# Top.net
KiCad netlist of a schematic drawn in Altium Designer
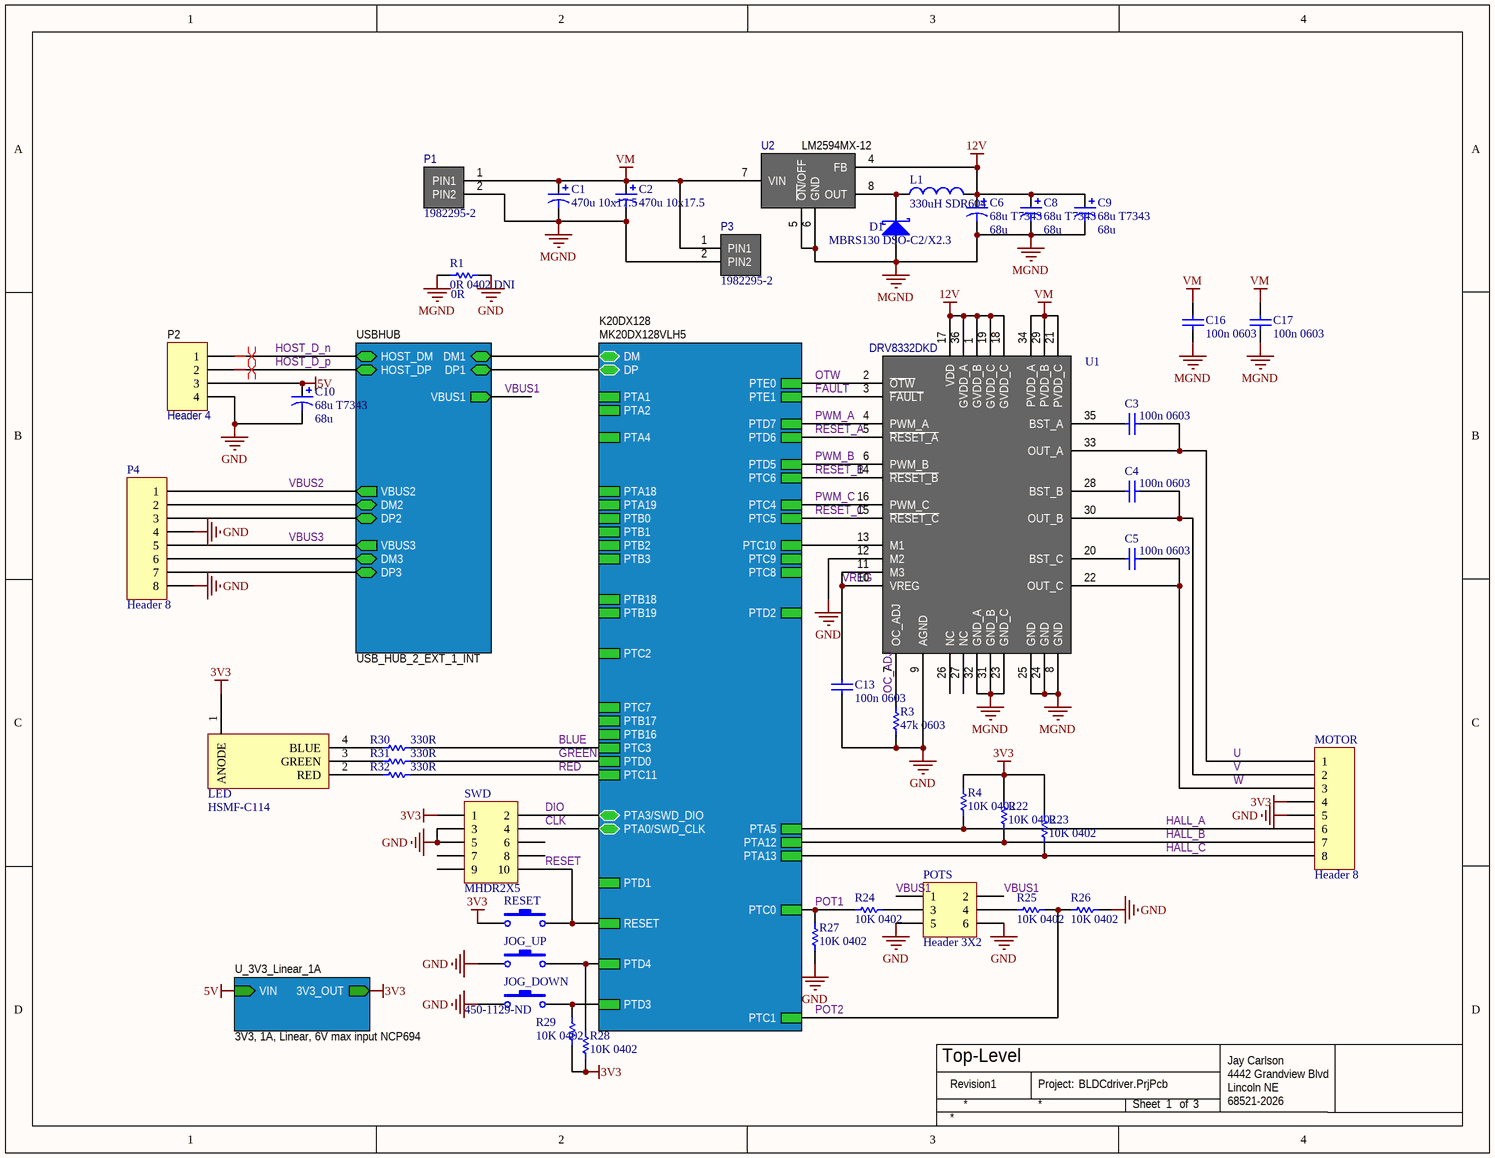
[diagram p0: Top.SchDoc]

(export (version "E")
  (design (tool "Eeschema 10.0.6"))
  (components
    (comp (ref "C1")
      (value "470u 10x17.5")
      (footprint "CAPPR5-10x17.5")
      (description "Polarized Capacitor (Radial)")
      (fields (field (name "PUBLISHER") "Altium Limited"))
      (libsource (lib "Miscellaneous Devices") (part "Cap Pol1"))
    )
    (comp (ref "C2")
      (value "470u 10x17.5")
      (footprint "CAPPR5-10x17.5")
      (description "Polarized Capacitor (Radial)")
      (fields (field (name "PUBLISHER") "Altium Limited"))
      (libsource (lib "Miscellaneous Devices") (part "Cap Pol1"))
    )
    (comp (ref "C3")
      (value "100n 0603")
      (footprint "CAPC1608N")
      (description "Capacitor")
      (fields (field (name "PUBLISHER") "Altium Limited"))
      (libsource (lib "Miscellaneous Devices") (part "Cap"))
    )
    (comp (ref "C4")
      (value "100n 0603")
      (footprint "CAPC1608N")
      (description "Capacitor")
      (fields (field (name "PUBLISHER") "Altium Limited"))
      (libsource (lib "Miscellaneous Devices") (part "Cap"))
    )
    (comp (ref "C5")
      (value "100n 0603")
      (footprint "CAPC1608N")
      (description "Capacitor")
      (fields (field (name "PUBLISHER") "Altium Limited"))
      (libsource (lib "Miscellaneous Devices") (part "Cap"))
    )
    (comp (ref "C6")
      (value "68u T7343")
      (footprint "TC7343-2917")
      (description "Polarized Capacitor (Radial)")
      (fields (field (name "ALTIUM_VALUE") "68u") (field (name "PUBLISHER") "Altium Limited"))
      (libsource (lib "Miscellaneous Devices") (part "Cap Pol1"))
    )
    (comp (ref "C8")
      (value "68u T7343")
      (footprint "TC7343-2917")
      (description "Polarized Capacitor (Radial)")
      (fields (field (name "ALTIUM_VALUE") "68u") (field (name "PUBLISHER") "Altium Limited"))
      (libsource (lib "Miscellaneous Devices") (part "Cap Pol1"))
    )
    (comp (ref "C9")
      (value "68u T7343")
      (footprint "TC7343-2917")
      (description "Polarized Capacitor (Radial)")
      (fields (field (name "ALTIUM_VALUE") "68u") (field (name "PUBLISHER") "Altium Limited"))
      (libsource (lib "Miscellaneous Devices") (part "Cap Pol1"))
    )
    (comp (ref "C10")
      (value "68u T7343")
      (footprint "TC7343-2917")
      (description "Polarized Capacitor (Radial)")
      (fields (field (name "ALTIUM_VALUE") "68u") (field (name "PUBLISHER") "Altium Limited"))
      (libsource (lib "Miscellaneous Devices") (part "Cap Pol1"))
    )
    (comp (ref "C13")
      (value "100n 0603")
      (footprint "CAPC1608N")
      (description "Capacitor")
      (fields (field (name "PUBLISHER") "Altium Limited"))
      (libsource (lib "Miscellaneous Devices") (part "Cap"))
    )
    (comp (ref "C16")
      (value "100n 0603")
      (footprint "CAPC1608N")
      (description "Capacitor")
      (fields (field (name "PUBLISHER") "Altium Limited"))
      (libsource (lib "Miscellaneous Devices") (part "Cap"))
    )
    (comp (ref "C17")
      (value "100n 0603")
      (footprint "CAPC1608N")
      (description "Capacitor")
      (fields (field (name "PUBLISHER") "Altium Limited"))
      (libsource (lib "Miscellaneous Devices") (part "Cap"))
    )
    (comp (ref "D1")
      (value "MBRS130 DSO-C2/X2.3")
      (footprint "DSO-C2/X2.3")
      (description "Schottky Diode")
      (fields (field (name "PUBLISHER") "Altium Limited"))
      (libsource (lib "Miscellaneous Devices") (part "D Schottky"))
    )
    (comp (ref "JOG_DOWN")
      (value "SW-PB")
      (footprint "SW/PB-SMD/H8")
      (description "Switch")
      (fields
        (field (name "SUPPLIER PART NUMBER 1") "450-1129-ND")
        (field (name "PUBLISHER") "Altium Limited")
      )
      (libsource (lib "Miscellaneous Devices") (part "SW-PB"))
    )
    (comp (ref "JOG_UP")
      (value "SW-PB")
      (footprint "SW/PB-SMD/H8")
      (description "Switch")
      (fields (field (name "PUBLISHER") "Altium Limited"))
      (libsource (lib "Miscellaneous Devices") (part "SW-PB"))
    )
    (comp (ref "L1")
      (value "330uH SDR604")
      (footprint "SDR604")
      (description "Inductor")
      (fields (field (name "PUBLISHER") "Altium Limited"))
      (libsource (lib "Miscellaneous Devices") (part "Inductor"))
    )
    (comp (ref "LED")
      (value "HSMF-C114")
      (footprint "HSMF-C114")
      (description "LED CHIP RGB 1.6X1.5X0.35MM SMD")
      (fields (field (name "MANUFACTURER") "Avago Technologies US Inc."))
      (libsource (lib "Avago Optoelectronic LED Custom") (part "HSMF-C114"))
    )
    (comp (ref "MOTOR")
      (value "Header 8")
      (footprint "7-215079-8")
      (description "Header, 8-Pin")
      (fields (field (name "PUBLISHER") "Altium Limited"))
      (libsource (lib "") (part "Header 8_1"))
    )
    (comp (ref "P1")
      (value "1982295-2")
      (footprint "1982295-2")
      (libsource (lib "TE Connectivity") (part "1982295-2"))
    )
    (comp (ref "P2")
      (value "Header 4")
      (footprint "USB2.5-2H4D")
      (description "Header, 4-Pin")
      (fields (field (name "PUBLISHER") "Altium Limited"))
      (libsource (lib "Miscellaneous Connectors") (part "Header 4"))
    )
    (comp (ref "P3") (value "1982295-2") (footprint "1982295-2") (libsource (lib "") (part "1982295-2_1")))
    (comp (ref "P4")
      (value "Header 8")
      (footprint "USB2.5-4H8")
      (description "Header, 8-Pin")
      (fields (field (name "PUBLISHER") "Altium Limited"))
      (libsource (lib "Miscellaneous Connectors") (part "Header 8"))
    )
    (comp (ref "POTS")
      (value "Header 3X2")
      (footprint "HDR2X3")
      (description "Header, 3-Pin, Dual row")
      (fields (field (name "PUBLISHER") "Altium Limited"))
      (libsource (lib "Miscellaneous Connectors") (part "Header 3X2"))
    )
    (comp (ref "R1")
      (value "0R 0402 DNI")
      (footprint "RESC1005N")
      (description "Semiconductor Resistor")
      (fields (field (name "ALTIUM_VALUE") "0R") (field (name "PUBLISHER") "Altium Limited"))
      (libsource (lib "Miscellaneous Devices") (part "Res Semi"))
    )
    (comp (ref "R3")
      (value "47k 0603")
      (footprint "RESC1608N")
      (description "Semiconductor Resistor")
      (fields (field (name "PUBLISHER") "Altium Limited"))
      (libsource (lib "Miscellaneous Devices") (part "Res Semi"))
    )
    (comp (ref "R4")
      (value "10K 0402")
      (footprint "RESC1005N")
      (description "Semiconductor Resistor")
      (fields (field (name "PUBLISHER") "Altium Limited"))
      (libsource (lib "Miscellaneous Devices") (part "Res Semi"))
    )
    (comp (ref "R22")
      (value "10K 0402")
      (footprint "RESC1005N")
      (description "Semiconductor Resistor")
      (fields (field (name "PUBLISHER") "Altium Limited"))
      (libsource (lib "Miscellaneous Devices") (part "Res Semi"))
    )
    (comp (ref "R23")
      (value "10K 0402")
      (footprint "RESC1005N")
      (description "Semiconductor Resistor")
      (fields (field (name "PUBLISHER") "Altium Limited"))
      (libsource (lib "Miscellaneous Devices") (part "Res Semi"))
    )
    (comp (ref "R24")
      (value "10K 0402")
      (footprint "RESC1005N")
      (description "Semiconductor Resistor")
      (fields (field (name "PUBLISHER") "Altium Limited"))
      (libsource (lib "Miscellaneous Devices") (part "Res Semi"))
    )
    (comp (ref "R25")
      (value "10K 0402")
      (footprint "RESC1005N")
      (description "Semiconductor Resistor")
      (fields (field (name "PUBLISHER") "Altium Limited"))
      (libsource (lib "Miscellaneous Devices") (part "Res Semi"))
    )
    (comp (ref "R26")
      (value "10K 0402")
      (footprint "RESC1005N")
      (description "Semiconductor Resistor")
      (fields (field (name "PUBLISHER") "Altium Limited"))
      (libsource (lib "Miscellaneous Devices") (part "Res Semi"))
    )
    (comp (ref "R27")
      (value "10K 0402")
      (footprint "RESC1005N")
      (description "Semiconductor Resistor")
      (fields (field (name "PUBLISHER") "Altium Limited"))
      (libsource (lib "Miscellaneous Devices") (part "Res Semi"))
    )
    (comp (ref "R28")
      (value "10K 0402")
      (footprint "RESC1005N")
      (description "Semiconductor Resistor")
      (fields (field (name "PUBLISHER") "Altium Limited"))
      (libsource (lib "Miscellaneous Devices") (part "Res Semi"))
    )
    (comp (ref "R29")
      (value "10K 0402")
      (footprint "RESC1005N")
      (description "Semiconductor Resistor")
      (fields (field (name "PUBLISHER") "Altium Limited"))
      (libsource (lib "Miscellaneous Devices") (part "Res Semi"))
    )
    (comp (ref "R30")
      (value "330R")
      (footprint "RESC1005N")
      (description "Semiconductor Resistor")
      (fields (field (name "Comment") "330R 0402") (field (name "PUBLISHER") "Altium Limited"))
      (libsource (lib "Miscellaneous Devices") (part "Res Semi"))
    )
    (comp (ref "R31")
      (value "330R")
      (footprint "RESC1005N")
      (description "Semiconductor Resistor")
      (fields (field (name "Comment") "330R 0402") (field (name "PUBLISHER") "Altium Limited"))
      (libsource (lib "Miscellaneous Devices") (part "Res Semi"))
    )
    (comp (ref "R32")
      (value "330R")
      (footprint "RESC1005N")
      (description "Semiconductor Resistor")
      (fields (field (name "Comment") "330R 0402") (field (name "PUBLISHER") "Altium Limited"))
      (libsource (lib "Miscellaneous Devices") (part "Res Semi"))
    )
    (comp (ref "RESET")
      (value "SW-PB")
      (footprint "SW/PB-SMD/H8")
      (description "Switch")
      (fields (field (name "PUBLISHER") "Altium Limited"))
      (libsource (lib "Miscellaneous Devices") (part "SW-PB"))
    )
    (comp (ref "SWD")
      (value "MHDR2X5")
      (footprint "MHDR2X5")
      (description "Header, 5-Pin, Dual row")
      (fields (field (name "PUBLISHER") "Altium Limited"))
      (libsource (lib "Miscellaneous Connectors") (part "MHDR2X5"))
    )
    (comp (ref "U1")
      (value "DRV8332DKD")
      (footprint "DKD36")
      (libsource (lib "TI Motor Driver") (part "DRV8332DKD"))
    )
    (comp (ref "U2")
      (value "LM2594MX-12")
      (footprint "SOIC127P600-8CN")
      (libsource (lib "TI Power Mgt Voltage Regulator Custom") (part "LM2594MX-12"))
    )
  )
  (nets
    (net (code "1") (name "/BLUE") (class "Default")
      (node (ref "R30") (pin "2") (pinfunction "2_2") (pintype "passive"))
    )
    (net (code "2") (name "/CLK") (class "Default")
      (node (ref "SWD") (pin "4") (pinfunction "4_4") (pintype "passive"))
    )
    (net (code "3") (name "/DIO") (class "Default")
      (node (ref "SWD") (pin "2") (pinfunction "2_2") (pintype "passive"))
    )
    (net (code "5") (name "/DM2") (class "Default")
      (node (ref "P4") (pin "2") (pinfunction "2_2") (pintype "passive"))
    )
    (net (code "6") (name "/DM3") (class "Default")
      (node (ref "P4") (pin "6") (pinfunction "6_6") (pintype "passive"))
    )
    (net (code "8") (name "/DP2") (class "Default")
      (node (ref "P4") (pin "3") (pinfunction "3_3") (pintype "passive"))
    )
    (net (code "9") (name "/DP3") (class "Default")
      (node (ref "P4") (pin "7") (pinfunction "7_7") (pintype "passive"))
    )
    (net (code "10") (name "/FAULT") (class "Default")
      (node (ref "U1") (pin "3") (pinfunction "~{FAULT}_3") (pintype "passive"))
    )
    (net (code "11") (name "/GREEN") (class "Default")
      (node (ref "R31") (pin "2") (pinfunction "2_2") (pintype "passive"))
    )
    (net (code "12") (name "/HALL_A") (class "Default")
      (node (ref "MOTOR") (pin "6") (pinfunction "6_6") (pintype "passive"))
      (node (ref "R4") (pin "2") (pinfunction "2_2") (pintype "passive"))
    )
    (net (code "13") (name "/HALL_B") (class "Default")
      (node (ref "MOTOR") (pin "7") (pinfunction "7_7") (pintype "passive"))
      (node (ref "R22") (pin "2") (pinfunction "2_2") (pintype "passive"))
    )
    (net (code "14") (name "/HALL_C") (class "Default")
      (node (ref "MOTOR") (pin "8") (pinfunction "8_8") (pintype "passive"))
      (node (ref "R23") (pin "2") (pinfunction "2_2") (pintype "passive"))
    )
    (net (code "15") (name "/HOST_D_n") (class "Default")
      (node (ref "P2") (pin "1") (pinfunction "1_1") (pintype "passive"))
    )
    (net (code "16") (name "/HOST_D_p") (class "Default")
      (node (ref "P2") (pin "2") (pinfunction "2_2") (pintype "passive"))
    )
    (net (code "17") (name "/OC_ADJ") (class "Default")
      (node (ref "R3") (pin "1") (pinfunction "1_1") (pintype "passive"))
      (node (ref "U1") (pin "7") (pinfunction "OC_ADJ_7") (pintype "passive"))
    )
    (net (code "18") (name "/OTW") (class "Default")
      (node (ref "U1") (pin "2") (pinfunction "~{OTW}_2") (pintype "passive"))
    )
    (net (code "19") (name "/POT1") (class "Default")
      (node (ref "R24") (pin "1") (pinfunction "1_1") (pintype "passive"))
      (node (ref "R27") (pin "1") (pinfunction "1_1") (pintype "passive"))
    )
    (net (code "20") (name "/POT2") (class "Default")
      (node (ref "R25") (pin "1") (pinfunction "1_1") (pintype "passive"))
      (node (ref "R26") (pin "1") (pinfunction "1_1") (pintype "passive"))
    )
    (net (code "38") (name "/PTC10") (class "Default")
      (node (ref "U1") (pin "13") (pinfunction "M1_13") (pintype "passive"))
    )
    (net (code "41") (name "/PTD3") (class "Default")
      (node (ref "JOG_DOWN") (pin "2") (pinfunction "2_2") (pintype "passive"))
      (node (ref "R29") (pin "1") (pinfunction "1_1") (pintype "passive"))
    )
    (net (code "42") (name "/PTD4") (class "Default")
      (node (ref "JOG_UP") (pin "2") (pinfunction "2_2") (pintype "passive"))
      (node (ref "R28") (pin "1") (pinfunction "1_1") (pintype "passive"))
    )
    (net (code "43") (name "/PWM_A") (class "Default")
      (node (ref "U1") (pin "4") (pinfunction "PWM_A_4") (pintype "passive"))
    )
    (net (code "44") (name "/PWM_B") (class "Default")
      (node (ref "U1") (pin "6") (pinfunction "PWM_B_6") (pintype "passive"))
    )
    (net (code "45") (name "/PWM_C") (class "Default")
      (node (ref "U1") (pin "16") (pinfunction "PWM_C_16") (pintype "passive"))
    )
    (net (code "46") (name "/RED") (class "Default")
      (node (ref "R32") (pin "2") (pinfunction "2_2") (pintype "passive"))
    )
    (net (code "47") (name "/RESET") (class "Default")
      (node (ref "RESET") (pin "2") (pinfunction "2_2") (pintype "passive"))
      (node (ref "SWD") (pin "10") (pinfunction "10_10") (pintype "passive"))
    )
    (net (code "48") (name "/RESET_A") (class "Default")
      (node (ref "U1") (pin "5") (pinfunction "~{RESET_A}_5") (pintype "passive"))
    )
    (net (code "49") (name "/RESET_B") (class "Default")
      (node (ref "U1") (pin "14") (pinfunction "~{RESET_B}_14") (pintype "passive"))
    )
    (net (code "50") (name "/RESET_C") (class "Default")
      (node (ref "U1") (pin "15") (pinfunction "~{RESET_C}_15") (pintype "passive"))
    )
    (net (code "51") (name "/U") (class "Default")
      (node (ref "C3") (pin "1") (pinfunction "1_1") (pintype "passive"))
      (node (ref "MOTOR") (pin "1") (pinfunction "1_1") (pintype "passive"))
      (node (ref "U1") (pin "33") (pinfunction "OUT_A_33") (pintype "passive"))
    )
    (net (code "52") (name "/V") (class "Default")
      (node (ref "C4") (pin "1") (pinfunction "1_1") (pintype "passive"))
      (node (ref "MOTOR") (pin "2") (pinfunction "2_2") (pintype "passive"))
      (node (ref "U1") (pin "30") (pinfunction "OUT_B_30") (pintype "passive"))
    )
    (net (code "53") (name "/VBUS1") (class "Default")
      (node (ref "POTS") (pin "1") (pinfunction "1_1") (pintype "passive"))
      (node (ref "POTS") (pin "2") (pinfunction "2_2") (pintype "passive"))
    )
    (net (code "54") (name "/VBUS2") (class "Default")
      (node (ref "P4") (pin "1") (pinfunction "1_1") (pintype "passive"))
    )
    (net (code "55") (name "/VBUS3") (class "Default")
      (node (ref "P4") (pin "5") (pinfunction "5_5") (pintype "passive"))
    )
    (net (code "56") (name "/VREG") (class "Default")
      (node (ref "C13") (pin "1") (pinfunction "1_1") (pintype "passive"))
      (node (ref "U1") (pin "10") (pinfunction "VREG_10") (pintype "passive"))
      (node (ref "U1") (pin "11") (pinfunction "M3_11") (pintype "passive"))
    )
    (net (code "57") (name "/W") (class "Default")
      (node (ref "C5") (pin "1") (pinfunction "1_1") (pintype "passive"))
      (node (ref "MOTOR") (pin "3") (pinfunction "3_3") (pintype "passive"))
      (node (ref "U1") (pin "22") (pinfunction "OUT_C_22") (pintype "passive"))
    )
    (net (code "58") (name "3V3") (class "Default")
      (node (ref "LED") (pin "1") (pinfunction "ANODE_1") (pintype "passive"))
      (node (ref "MOTOR") (pin "4") (pinfunction "4_4") (pintype "passive"))
      (node (ref "R22") (pin "1") (pinfunction "1_1") (pintype "passive"))
      (node (ref "R23") (pin "1") (pinfunction "1_1") (pintype "passive"))
      (node (ref "R28") (pin "2") (pinfunction "2_2") (pintype "passive"))
      (node (ref "R29") (pin "2") (pinfunction "2_2") (pintype "passive"))
      (node (ref "R4") (pin "1") (pinfunction "1_1") (pintype "passive"))
      (node (ref "RESET") (pin "1") (pinfunction "1_1") (pintype "passive"))
      (node (ref "SWD") (pin "1") (pinfunction "1_1") (pintype "passive"))
    )
    (net (code "59") (name "5V") (class "Default")
      (node (ref "C10") (pin "1") (pinfunction "1_1") (pintype "passive"))
      (node (ref "P2") (pin "3") (pinfunction "3_3") (pintype "passive"))
    )
    (net (code "60") (name "12V") (class "Default")
      (node (ref "C6") (pin "1") (pinfunction "1_1") (pintype "passive"))
      (node (ref "C8") (pin "1") (pinfunction "1_1") (pintype "passive"))
      (node (ref "C9") (pin "1") (pinfunction "1_1") (pintype "passive"))
      (node (ref "L1") (pin "2") (pinfunction "2_2") (pintype "passive"))
      (node (ref "U1") (pin "1") (pinfunction "GVDD_B_1") (pintype "passive"))
      (node (ref "U1") (pin "17") (pinfunction "VDD_17") (pintype "passive"))
      (node (ref "U1") (pin "18") (pinfunction "GVDD_C_18") (pintype "passive"))
      (node (ref "U1") (pin "19") (pinfunction "GVDD_C_19") (pintype "passive"))
      (node (ref "U1") (pin "36") (pinfunction "GVDD_A_36") (pintype "passive"))
      (node (ref "U2") (pin "4") (pinfunction "FB_4") (pintype "power_in"))
    )
    (net (code "61") (name "GND") (class "Default")
      (node (ref "C10") (pin "2") (pinfunction "2_2") (pintype "passive"))
      (node (ref "C13") (pin "2") (pinfunction "2_2") (pintype "passive"))
      (node (ref "JOG_DOWN") (pin "1") (pinfunction "1_1") (pintype "passive"))
      (node (ref "JOG_UP") (pin "1") (pinfunction "1_1") (pintype "passive"))
      (node (ref "MOTOR") (pin "5") (pinfunction "5_5") (pintype "passive"))
      (node (ref "P2") (pin "4") (pinfunction "4_4") (pintype "passive"))
      (node (ref "P4") (pin "4") (pinfunction "4_4") (pintype "passive"))
      (node (ref "P4") (pin "8") (pinfunction "8_8") (pintype "passive"))
      (node (ref "POTS") (pin "5") (pinfunction "5_5") (pintype "passive"))
      (node (ref "POTS") (pin "6") (pinfunction "6_6") (pintype "passive"))
      (node (ref "R1") (pin "1") (pinfunction "1_1") (pintype "passive"))
      (node (ref "R26") (pin "2") (pinfunction "2_2") (pintype "passive"))
      (node (ref "R27") (pin "2") (pinfunction "2_2") (pintype "passive"))
      (node (ref "R3") (pin "2") (pinfunction "2_2") (pintype "passive"))
      (node (ref "SWD") (pin "3") (pinfunction "3_3") (pintype "passive"))
      (node (ref "SWD") (pin "5") (pinfunction "5_5") (pintype "passive"))
      (node (ref "U1") (pin "12") (pinfunction "M2_12") (pintype "passive"))
      (node (ref "U1") (pin "9") (pinfunction "AGND_9") (pintype "passive"))
    )
    (net (code "62") (name "MGND") (class "Default")
      (node (ref "C1") (pin "2") (pinfunction "2_2") (pintype "passive"))
      (node (ref "C16") (pin "2") (pinfunction "2_2") (pintype "passive"))
      (node (ref "C17") (pin "2") (pinfunction "2_2") (pintype "passive"))
      (node (ref "C2") (pin "2") (pinfunction "2_2") (pintype "passive"))
      (node (ref "C6") (pin "2") (pinfunction "2_2") (pintype "passive"))
      (node (ref "C8") (pin "2") (pinfunction "2_2") (pintype "passive"))
      (node (ref "C9") (pin "2") (pinfunction "2_2") (pintype "passive"))
      (node (ref "D1") (pin "1") (pinfunction "A_1") (pintype "passive"))
      (node (ref "P1") (pin "2") (pinfunction "PIN2_2") (pintype "power_in"))
      (node (ref "P3") (pin "2") (pinfunction "PIN2_2") (pintype "power_in"))
      (node (ref "R1") (pin "2") (pinfunction "2_2") (pintype "passive"))
      (node (ref "U1") (pin "23") (pinfunction "GND_C_23") (pintype "passive"))
      (node (ref "U1") (pin "24") (pinfunction "GND_24") (pintype "passive"))
      (node (ref "U1") (pin "25") (pinfunction "GND_25") (pintype "passive"))
      (node (ref "U1") (pin "31") (pinfunction "GND_B_31") (pintype "passive"))
      (node (ref "U1") (pin "32") (pinfunction "GND_A_32") (pintype "passive"))
      (node (ref "U1") (pin "8") (pinfunction "GND_8") (pintype "passive"))
      (node (ref "U2") (pin "5") (pinfunction "~{ON}/OFF_5") (pintype "power_in"))
      (node (ref "U2") (pin "6") (pinfunction "GND_6") (pintype "power_in"))
    )
    (net (code "63") (name "Net-(D1-K)") (class "Default")
      (node (ref "D1") (pin "2") (pinfunction "K_2") (pintype "passive"))
      (node (ref "L1") (pin "1") (pinfunction "1_1") (pintype "passive"))
      (node (ref "U2") (pin "8") (pinfunction "OUT_8") (pintype "power_in"))
    )
    (net (code "64") (name "Net-(LED-BLUE)") (class "Default")
      (node (ref "LED") (pin "4") (pinfunction "BLUE_4") (pintype "passive"))
      (node (ref "R30") (pin "1") (pinfunction "1_1") (pintype "passive"))
    )
    (net (code "65") (name "Net-(LED-GREEN)") (class "Default")
      (node (ref "LED") (pin "3") (pinfunction "GREEN_3") (pintype "passive"))
      (node (ref "R31") (pin "1") (pinfunction "1_1") (pintype "passive"))
    )
    (net (code "66") (name "Net-(LED-RED)") (class "Default")
      (node (ref "LED") (pin "2") (pinfunction "RED_2") (pintype "passive"))
      (node (ref "R32") (pin "1") (pinfunction "1_1") (pintype "passive"))
    )
    (net (code "67") (name "Net-(POTS-Pad3)") (class "Default")
      (node (ref "POTS") (pin "3") (pinfunction "3_3") (pintype "passive"))
      (node (ref "R24") (pin "2") (pinfunction "2_2") (pintype "passive"))
    )
    (net (code "68") (name "Net-(POTS-Pad4)") (class "Default")
      (node (ref "POTS") (pin "4") (pinfunction "4_4") (pintype "passive"))
      (node (ref "R25") (pin "2") (pinfunction "2_2") (pintype "passive"))
    )
    (net (code "69") (name "Net-(U1-BST_A)") (class "Default")
      (node (ref "C3") (pin "2") (pinfunction "2_2") (pintype "passive"))
      (node (ref "U1") (pin "35") (pinfunction "BST_A_35") (pintype "passive"))
    )
    (net (code "70") (name "Net-(U1-BST_B)") (class "Default")
      (node (ref "C4") (pin "2") (pinfunction "2_2") (pintype "passive"))
      (node (ref "U1") (pin "28") (pinfunction "BST_B_28") (pintype "passive"))
    )
    (net (code "71") (name "Net-(U1-BST_C)") (class "Default")
      (node (ref "C5") (pin "2") (pinfunction "2_2") (pintype "passive"))
      (node (ref "U1") (pin "20") (pinfunction "BST_C_20") (pintype "passive"))
    )
    (net (code "72") (name "VM") (class "Default")
      (node (ref "C1") (pin "1") (pinfunction "1_1") (pintype "passive"))
      (node (ref "C16") (pin "1") (pinfunction "1_1") (pintype "passive"))
      (node (ref "C17") (pin "1") (pinfunction "1_1") (pintype "passive"))
      (node (ref "C2") (pin "1") (pinfunction "1_1") (pintype "passive"))
      (node (ref "P1") (pin "1") (pinfunction "PIN1_1") (pintype "power_in"))
      (node (ref "P3") (pin "1") (pinfunction "PIN1_1") (pintype "power_in"))
      (node (ref "U1") (pin "21") (pinfunction "PVDD_C_21") (pintype "passive"))
      (node (ref "U1") (pin "29") (pinfunction "PVDD_B_29") (pintype "passive"))
      (node (ref "U1") (pin "34") (pinfunction "PVDD_A_34") (pintype "passive"))
      (node (ref "U2") (pin "7") (pinfunction "VIN_7") (pintype "power_in"))
    )
    (net (code "73") (name "unconnected-(SWD-Pad6)") (class "Default")
      (node (ref "SWD") (pin "6") (pinfunction "6_6") (pintype "passive"))
    )
    (net (code "74") (name "unconnected-(SWD-Pad7)") (class "Default")
      (node (ref "SWD") (pin "7") (pinfunction "7_7") (pintype "passive"))
    )
    (net (code "75") (name "unconnected-(SWD-Pad8)") (class "Default")
      (node (ref "SWD") (pin "8") (pinfunction "8_8") (pintype "passive"))
    )
    (net (code "76") (name "unconnected-(SWD-Pad9)") (class "Default")
      (node (ref "SWD") (pin "9") (pinfunction "9_9") (pintype "passive"))
    )
    (net (code "77") (name "unconnected-(U1-NC-Pad26)") (class "Default")
      (node (ref "U1") (pin "26") (pinfunction "NC_26") (pintype "passive"))
    )
    (net (code "78") (name "unconnected-(U1-NC-Pad27)") (class "Default")
      (node (ref "U1") (pin "27") (pinfunction "NC_27") (pintype "passive"))
    )
  )
)
